# mainboard_valdis.net
KiCad netlist of a schematic drawn in Altium Designer
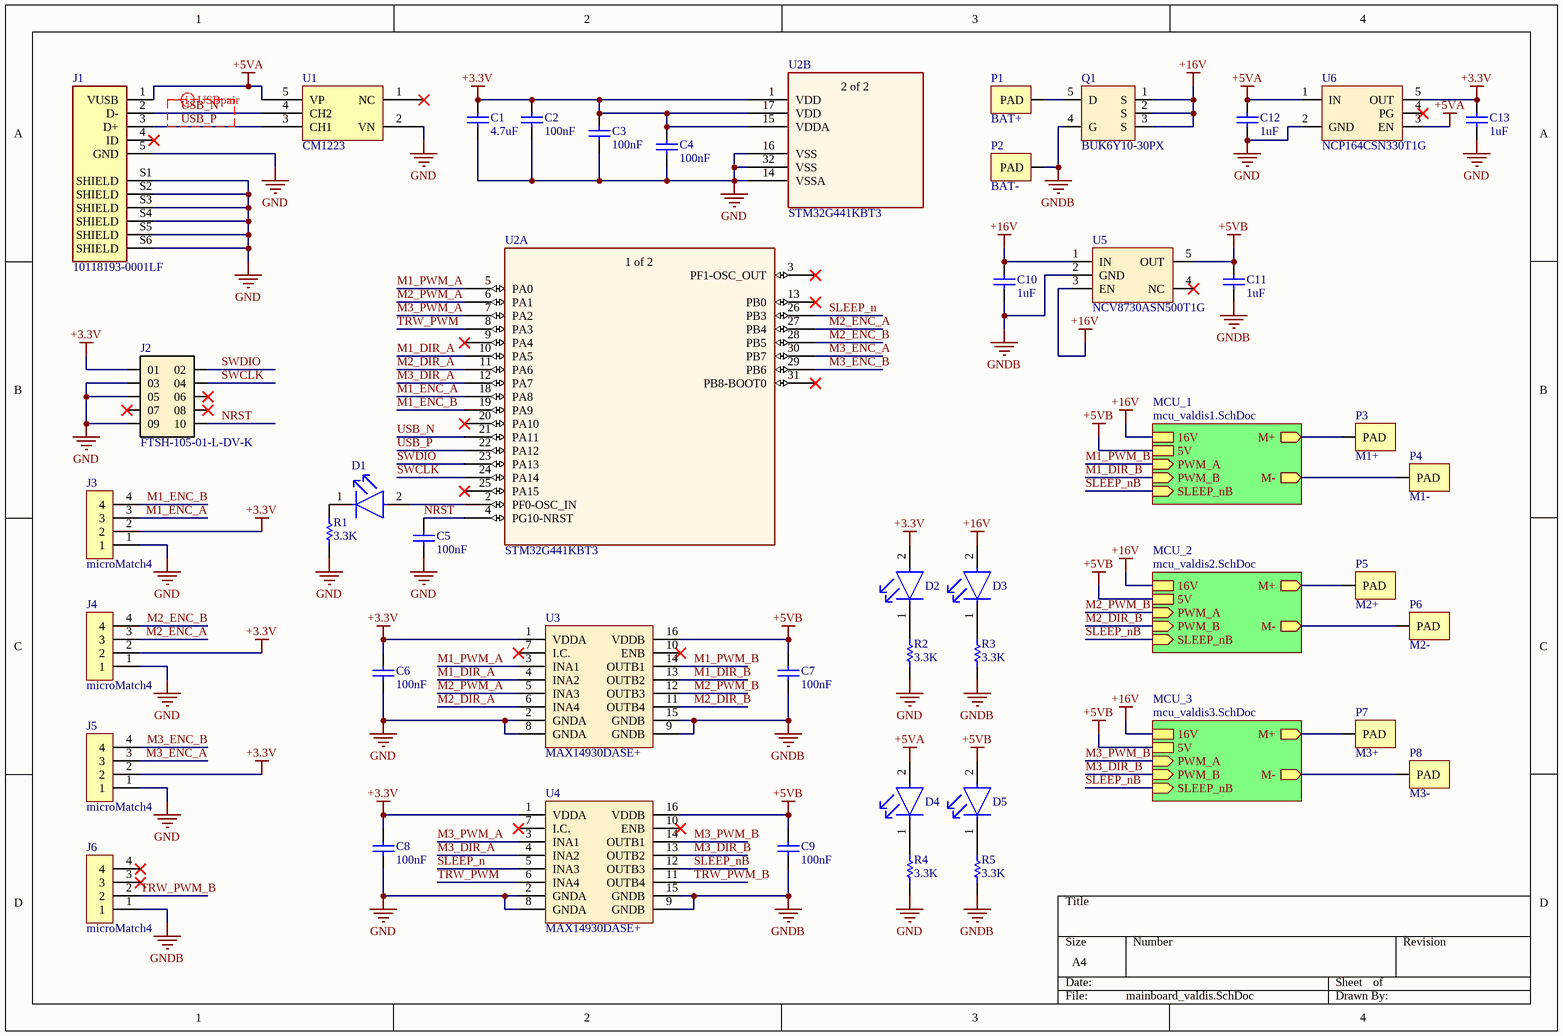
[diagram p0: mainboard_valdis.SchDoc]

(export (version "E")
  (design (tool "Eeschema 10.0.6"))
  (components
    (comp (ref "C1")
      (value "4.7uF")
      (footprint "CAPC1608X90X35ML10T15")
      (description "Chip Capacitor, 22 pF, +/- 5%, 50 V, -55 to 125 degC, 0603 (1608 Metric), RoHS, Tape and Reel")
      (fields (field (name "MANUFACTURER") "Murata"))
      (libsource (lib "Altium Content Vault") (part "CAP-NP-2"))
    )
    (comp (ref "C2")
      (value "100nF")
      (footprint "CAPC1608X90X35ML10T15")
      (description "Chip Capacitor, 22 pF, +/- 5%, 50 V, -55 to 125 degC, 0603 (1608 Metric), RoHS, Tape and Reel")
      (fields (field (name "MANUFACTURER") "Murata"))
      (libsource (lib "Altium Content Vault") (part "CAP-NP-2"))
    )
    (comp (ref "C3")
      (value "100nF")
      (footprint "CAPC1608X90X35ML10T15")
      (description "Chip Capacitor, 22 pF, +/- 5%, 50 V, -55 to 125 degC, 0603 (1608 Metric), RoHS, Tape and Reel")
      (fields (field (name "MANUFACTURER") "Murata"))
      (libsource (lib "Altium Content Vault") (part "CAP-NP-2"))
    )
    (comp (ref "C4")
      (value "100nF")
      (footprint "CAPC1608X90X35ML10T15")
      (description "Chip Capacitor, 22 pF, +/- 5%, 50 V, -55 to 125 degC, 0603 (1608 Metric), RoHS, Tape and Reel")
      (fields (field (name "MANUFACTURER") "Murata"))
      (libsource (lib "Altium Content Vault") (part "CAP-NP-2"))
    )
    (comp (ref "C5")
      (value "100nF")
      (footprint "CAPC1608X90X35ML10T15")
      (description "Chip Capacitor, 22 pF, +/- 5%, 50 V, -55 to 125 degC, 0603 (1608 Metric), RoHS, Tape and Reel")
      (fields (field (name "MANUFACTURER") "Murata"))
      (libsource (lib "Altium Content Vault") (part "CAP-NP-2"))
    )
    (comp (ref "C6")
      (value "100nF")
      (footprint "CAPC1608X90X35ML10T15")
      (description "Chip Capacitor, 22 pF, +/- 5%, 50 V, -55 to 125 degC, 0603 (1608 Metric), RoHS, Tape and Reel")
      (fields (field (name "MANUFACTURER") "Murata"))
      (libsource (lib "Altium Content Vault") (part "CAP-NP-2"))
    )
    (comp (ref "C7")
      (value "100nF")
      (footprint "CAPC1608X90X35ML10T15")
      (description "Chip Capacitor, 22 pF, +/- 5%, 50 V, -55 to 125 degC, 0603 (1608 Metric), RoHS, Tape and Reel")
      (fields (field (name "MANUFACTURER") "Murata"))
      (libsource (lib "Altium Content Vault") (part "CAP-NP-2"))
    )
    (comp (ref "C8")
      (value "100nF")
      (footprint "CAPC1608X90X35ML10T15")
      (description "Chip Capacitor, 22 pF, +/- 5%, 50 V, -55 to 125 degC, 0603 (1608 Metric), RoHS, Tape and Reel")
      (fields (field (name "MANUFACTURER") "Murata"))
      (libsource (lib "Altium Content Vault") (part "CAP-NP-2"))
    )
    (comp (ref "C9")
      (value "100nF")
      (footprint "CAPC1608X90X35ML10T15")
      (description "Chip Capacitor, 22 pF, +/- 5%, 50 V, -55 to 125 degC, 0603 (1608 Metric), RoHS, Tape and Reel")
      (fields (field (name "MANUFACTURER") "Murata"))
      (libsource (lib "Altium Content Vault") (part "CAP-NP-2"))
    )
    (comp (ref "C10")
      (value "1uF")
      (footprint "CAPC1608X90X35ML10T15")
      (description "Chip Capacitor, 22 pF, +/- 5%, 50 V, -55 to 125 degC, 0603 (1608 Metric), RoHS, Tape and Reel")
      (fields (field (name "MANUFACTURER") "Murata"))
      (libsource (lib "Altium Content Vault") (part "CAP-NP-2"))
    )
    (comp (ref "C11")
      (value "1uF")
      (footprint "CAPC1608X90X35ML10T15")
      (description "Chip Capacitor, 22 pF, +/- 5%, 50 V, -55 to 125 degC, 0603 (1608 Metric), RoHS, Tape and Reel")
      (fields (field (name "MANUFACTURER") "Murata"))
      (libsource (lib "Altium Content Vault") (part "CAP-NP-2"))
    )
    (comp (ref "C12")
      (value "1uF")
      (footprint "CAPC1608X90X35ML10T15")
      (description "Chip Capacitor, 22 pF, +/- 5%, 50 V, -55 to 125 degC, 0603 (1608 Metric), RoHS, Tape and Reel")
      (fields (field (name "MANUFACTURER") "Murata"))
      (libsource (lib "Altium Content Vault") (part "CAP-NP-2"))
    )
    (comp (ref "C13")
      (value "1uF")
      (footprint "CAPC1608X90X35ML10T15")
      (description "Chip Capacitor, 22 pF, +/- 5%, 50 V, -55 to 125 degC, 0603 (1608 Metric), RoHS, Tape and Reel")
      (fields (field (name "MANUFACTURER") "Murata"))
      (libsource (lib "Altium Content Vault") (part "CAP-NP-2"))
    )
    (comp (ref "D1")
      (value "LTST-C191TBKT")
      (footprint "FP-LTST-C191TBKT-MFG")
      (description "LED BLUE CLEAR CHIP SMD")
      (libsource (lib "Altium Content Vault") (part "8706943c75ba83719d021d2fdc84c58"))
    )
    (comp (ref "D2")
      (value "LTST-C191TBKT")
      (footprint "FP-LTST-C191TBKT-MFG")
      (description "LED BLUE CLEAR CHIP SMD")
      (libsource (lib "Altium Content Vault") (part "8706943c75ba83719d021d2fdc84c58"))
    )
    (comp (ref "D3")
      (value "LTST-C191TBKT")
      (footprint "FP-LTST-C191TBKT-MFG")
      (description "LED BLUE CLEAR CHIP SMD")
      (libsource (lib "Altium Content Vault") (part "8706943c75ba83719d021d2fdc84c58"))
    )
    (comp (ref "D4")
      (value "LTST-C191TBKT")
      (footprint "FP-LTST-C191TBKT-MFG")
      (description "LED BLUE CLEAR CHIP SMD")
      (libsource (lib "Altium Content Vault") (part "8706943c75ba83719d021d2fdc84c58"))
    )
    (comp (ref "D5")
      (value "LTST-C191TBKT")
      (footprint "FP-LTST-C191TBKT-MFG")
      (description "LED BLUE CLEAR CHIP SMD")
      (libsource (lib "Altium Content Vault") (part "8706943c75ba83719d021d2fdc84c58"))
    )
    (comp (ref "J1")
      (value "10118193-0001LF")
      (footprint "FCI_10118193-0001LF")
      (description "USB - micro B USB 2.0 Receptacle Connector 5 Position Surface Mount, Right Angle; Through Hole")
      (fields (field (name "MF") "Amphenol ICC"))
      (libsource (lib "Valdis_Components") (part "10118193-0001LF"))
    )
    (comp (ref "J2")
      (value "FTSH-105-01-L-DV-K")
      (footprint "FTSH-105-01-XXX-DV-K")
      (libsource (lib "Valdis_Components") (part "FTSH-105-01-L-DV-K"))
    )
    (comp (ref "J3")
      (value "microMatch4")
      (footprint "microMatch4:microMatch4")
      (libsource (lib "Valdis_Components") (part "microMatch4"))
    )
    (comp (ref "J4")
      (value "microMatch4")
      (footprint "microMatch4:microMatch4")
      (libsource (lib "Valdis_Components") (part "microMatch4"))
    )
    (comp (ref "J5")
      (value "microMatch4")
      (footprint "microMatch4:microMatch4")
      (libsource (lib "Valdis_Components") (part "microMatch4"))
    )
    (comp (ref "J6")
      (value "microMatch4")
      (footprint "microMatch4:microMatch4")
      (libsource (lib "Valdis_Components") (part "microMatch4"))
    )
    (comp (ref "P1") (value "BAT+") (footprint "PCBComponent_1") (libsource (lib "") (part "Pad4x4_1")))
    (comp (ref "P2") (value "BAT-") (footprint "PCBComponent_1") (libsource (lib "") (part "Pad4x4_1")))
    (comp (ref "P3")
      (value "M1+")
      (footprint "PCBComponent_1")
      (libsource (lib "Valdis_Components") (part "Pad4x4"))
    )
    (comp (ref "P4")
      (value "M1-")
      (footprint "PCBComponent_1")
      (libsource (lib "Valdis_Components") (part "Pad4x4"))
    )
    (comp (ref "P5")
      (value "M2+")
      (footprint "PCBComponent_1")
      (libsource (lib "Valdis_Components") (part "Pad4x4"))
    )
    (comp (ref "P6")
      (value "M2-")
      (footprint "PCBComponent_1")
      (libsource (lib "Valdis_Components") (part "Pad4x4"))
    )
    (comp (ref "P7")
      (value "M3+")
      (footprint "PCBComponent_1")
      (libsource (lib "Valdis_Components") (part "Pad4x4"))
    )
    (comp (ref "P8")
      (value "M3-")
      (footprint "PCBComponent_1")
      (libsource (lib "Valdis_Components") (part "Pad4x4"))
    )
    (comp (ref "Q1")
      (value "BUK6Y10-30PX")
      (footprint "TO127P600X120-5N")
      (libsource (lib "Valdis_Components") (part "BUK6Y10-30PX"))
    )
    (comp (ref "R1")
      (value "3.3K")
      (footprint "RESC1609X50X30NL8T20")
      (description "Chip Resistor, 0 Ohm, Jumper, 100 mW, -55 to 155 degC, 0603 (1608 Metric), RoHS, Tape and Reel")
      (fields (field (name "MANUFACTURER") "Vishay Semiconductor"))
      (libsource (lib "Altium Content Vault") (part "RES-2"))
    )
    (comp (ref "R2")
      (value "3.3K")
      (footprint "RESC1609X50X30NL8T20")
      (description "Chip Resistor, 0 Ohm, Jumper, 100 mW, -55 to 155 degC, 0603 (1608 Metric), RoHS, Tape and Reel")
      (fields (field (name "MANUFACTURER") "Vishay Semiconductor"))
      (libsource (lib "Altium Content Vault") (part "RES-2"))
    )
    (comp (ref "R3")
      (value "3.3K")
      (footprint "RESC1609X50X30NL8T20")
      (description "Chip Resistor, 0 Ohm, Jumper, 100 mW, -55 to 155 degC, 0603 (1608 Metric), RoHS, Tape and Reel")
      (fields (field (name "MANUFACTURER") "Vishay Semiconductor"))
      (libsource (lib "Altium Content Vault") (part "RES-2"))
    )
    (comp (ref "R4")
      (value "3.3K")
      (footprint "RESC1609X50X30NL8T20")
      (description "Chip Resistor, 0 Ohm, Jumper, 100 mW, -55 to 155 degC, 0603 (1608 Metric), RoHS, Tape and Reel")
      (fields (field (name "MANUFACTURER") "Vishay Semiconductor"))
      (libsource (lib "Altium Content Vault") (part "RES-2"))
    )
    (comp (ref "R5")
      (value "3.3K")
      (footprint "RESC1609X50X30NL8T20")
      (description "Chip Resistor, 0 Ohm, Jumper, 100 mW, -55 to 155 degC, 0603 (1608 Metric), RoHS, Tape and Reel")
      (fields (field (name "MANUFACTURER") "Vishay Semiconductor"))
      (libsource (lib "Altium Content Vault") (part "RES-2"))
    )
    (comp (ref "U1")
      (value "CM1223")
      (footprint "SOT23-5")
      (libsource (lib "Valdis_Components") (part "CM1223"))
    )
    (comp (ref "U2")
      (value "STM32G441KBT3")
      (footprint "LQFP32_7X7_STM")
      (description "No Description Available")
      (fields (field (name "COPYRIGHT") "Copyright (C) 2018 Accelerated Designs. All rights reserved"))
      (libsource (lib "") (part "STM32G441KBT3_1"))
    )
    (comp (ref "U3")
      (value "MAX14930DASE+")
      (footprint "21-0041_S16+1_MXM")
      (libsource (lib "Valdis_Components") (part "MAX14930DASE+"))
    )
    (comp (ref "U4")
      (value "MAX14930DASE+")
      (footprint "21-0041_S16+1_MXM")
      (libsource (lib "Valdis_Components") (part "MAX14930DASE+"))
    )
    (comp (ref "U5")
      (value "NCV8730ASN500T1G")
      (footprint "NCV8730:TSSOP5")
      (libsource (lib "NCV8730ASN500T1G") (part "NCV8730ASN500T1G"))
    )
    (comp (ref "U6")
      (value "NCP164CSN330T1G")
      (footprint "SOP95P275X110-5N")
      (libsource (lib "Valdis_Components") (part "NCP164CSN330T1G"))
    )
  )
  (nets
    (net (code "1") (name "+3.3V") (class "Default")
      (node (ref "C1") (pin "2") (pinfunction "2_2") (pintype "passive"))
      (node (ref "C13") (pin "2") (pinfunction "2_2") (pintype "passive"))
      (node (ref "C2") (pin "2") (pinfunction "2_2") (pintype "passive"))
      (node (ref "C3") (pin "2") (pinfunction "2_2") (pintype "passive"))
      (node (ref "C4") (pin "2") (pinfunction "2_2") (pintype "passive"))
      (node (ref "C6") (pin "2") (pinfunction "2_2") (pintype "passive"))
      (node (ref "C8") (pin "2") (pinfunction "2_2") (pintype "passive"))
      (node (ref "D2") (pin "2") (pinfunction "A_2") (pintype "passive"))
      (node (ref "J2") (pin "1") (pinfunction "01_1") (pintype "passive"))
      (node (ref "J3") (pin "2") (pinfunction "2_2") (pintype "passive"))
      (node (ref "J4") (pin "2") (pinfunction "2_2") (pintype "passive"))
      (node (ref "J5") (pin "2") (pinfunction "2_2") (pintype "passive"))
      (node (ref "U2") (pin "1") (pinfunction "VDD_1") (pintype "power_in"))
      (node (ref "U2") (pin "15") (pinfunction "VDDA_15") (pintype "power_in"))
      (node (ref "U2") (pin "17") (pinfunction "VDD_17") (pintype "power_in"))
      (node (ref "U3") (pin "1") (pinfunction "VDDA_1") (pintype "passive"))
      (node (ref "U4") (pin "1") (pinfunction "VDDA_1") (pintype "passive"))
      (node (ref "U6") (pin "5") (pinfunction "OUT_5") (pintype "passive"))
    )
    (net (code "2") (name "+5VA") (class "Default")
      (node (ref "C12") (pin "2") (pinfunction "2_2") (pintype "passive"))
      (node (ref "D4") (pin "2") (pinfunction "A_2") (pintype "passive"))
      (node (ref "J1") (pin "1") (pinfunction "VUSB_1") (pintype "passive"))
      (node (ref "U1") (pin "5") (pinfunction "VP_5") (pintype "passive"))
      (node (ref "U6") (pin "1") (pinfunction "IN_1") (pintype "passive"))
      (node (ref "U6") (pin "3") (pinfunction "EN_3") (pintype "passive"))
    )
    (net (code "3") (name "+5VB") (class "Default")
      (node (ref "C11") (pin "2") (pinfunction "2_2") (pintype "passive"))
      (node (ref "C7") (pin "2") (pinfunction "2_2") (pintype "passive"))
      (node (ref "C9") (pin "2") (pinfunction "2_2") (pintype "passive"))
      (node (ref "D5") (pin "2") (pinfunction "A_2") (pintype "passive"))
      (node (ref "U3") (pin "16") (pinfunction "VDDB_16") (pintype "passive"))
      (node (ref "U4") (pin "16") (pinfunction "VDDB_16") (pintype "passive"))
      (node (ref "U5") (pin "5") (pinfunction "OUT_5") (pintype "passive"))
    )
    (net (code "4") (name "+16V") (class "Default")
      (node (ref "C10") (pin "2") (pinfunction "2_2") (pintype "passive"))
      (node (ref "D3") (pin "2") (pinfunction "A_2") (pintype "passive"))
      (node (ref "Q1") (pin "1") (pinfunction "S_1") (pintype "passive"))
      (node (ref "Q1") (pin "2") (pinfunction "S_2") (pintype "passive"))
      (node (ref "Q1") (pin "3") (pinfunction "S_3") (pintype "passive"))
      (node (ref "U5") (pin "1") (pinfunction "IN_1") (pintype "passive"))
      (node (ref "U5") (pin "3") (pinfunction "EN_3") (pintype "passive"))
    )
    (net (code "5") (name "/M+") (class "Default")
      (node (ref "P7") (pin "1") (pinfunction "PAD_1") (pintype "passive"))
    )
    (net (code "6") (name "/M+_1") (class "Default")
      (node (ref "P3") (pin "1") (pinfunction "PAD_1") (pintype "passive"))
    )
    (net (code "7") (name "/M+_2") (class "Default")
      (node (ref "P5") (pin "1") (pinfunction "PAD_1") (pintype "passive"))
    )
    (net (code "8") (name "/M-") (class "Default")
      (node (ref "P8") (pin "1") (pinfunction "PAD_1") (pintype "passive"))
    )
    (net (code "9") (name "/M-_1") (class "Default")
      (node (ref "P4") (pin "1") (pinfunction "PAD_1") (pintype "passive"))
    )
    (net (code "10") (name "/M-_2") (class "Default")
      (node (ref "P6") (pin "1") (pinfunction "PAD_1") (pintype "passive"))
    )
    (net (code "11") (name "/M1_DIR_A") (class "Default")
      (node (ref "U2") (pin "10") (pinfunction "PA5_10") (pintype "bidirectional"))
      (node (ref "U3") (pin "4") (pinfunction "INA2_4") (pintype "passive"))
    )
    (net (code "12") (name "/M1_DIR_B") (class "Default")
      (node (ref "U3") (pin "13") (pinfunction "OUTB2_13") (pintype "passive"))
    )
    (net (code "13") (name "/M1_ENC_A") (class "Default")
      (node (ref "J3") (pin "3") (pinfunction "3_3") (pintype "passive"))
      (node (ref "U2") (pin "18") (pinfunction "PA8_18") (pintype "bidirectional"))
    )
    (net (code "14") (name "/M1_ENC_B") (class "Default")
      (node (ref "J3") (pin "4") (pinfunction "4_4") (pintype "passive"))
      (node (ref "U2") (pin "19") (pinfunction "PA9_19") (pintype "bidirectional"))
    )
    (net (code "15") (name "/M1_PWM_A") (class "Default")
      (node (ref "U2") (pin "5") (pinfunction "PA0_5") (pintype "bidirectional"))
      (node (ref "U3") (pin "3") (pinfunction "INA1_3") (pintype "passive"))
    )
    (net (code "16") (name "/M1_PWM_B") (class "Default")
      (node (ref "U3") (pin "14") (pinfunction "OUTB1_14") (pintype "passive"))
    )
    (net (code "17") (name "/M2_DIR_A") (class "Default")
      (node (ref "U2") (pin "11") (pinfunction "PA6_11") (pintype "bidirectional"))
      (node (ref "U3") (pin "6") (pinfunction "INA4_6") (pintype "passive"))
    )
    (net (code "18") (name "/M2_DIR_B") (class "Default")
      (node (ref "U3") (pin "11") (pinfunction "OUTB4_11") (pintype "passive"))
    )
    (net (code "19") (name "/M2_ENC_A") (class "Default")
      (node (ref "J4") (pin "3") (pinfunction "3_3") (pintype "passive"))
      (node (ref "U2") (pin "27") (pinfunction "PB4_27") (pintype "bidirectional"))
    )
    (net (code "20") (name "/M2_ENC_B") (class "Default")
      (node (ref "J4") (pin "4") (pinfunction "4_4") (pintype "passive"))
      (node (ref "U2") (pin "28") (pinfunction "PB5_28") (pintype "bidirectional"))
    )
    (net (code "21") (name "/M2_PWM_A") (class "Default")
      (node (ref "U2") (pin "6") (pinfunction "PA1_6") (pintype "bidirectional"))
      (node (ref "U3") (pin "5") (pinfunction "INA3_5") (pintype "passive"))
    )
    (net (code "22") (name "/M2_PWM_B") (class "Default")
      (node (ref "U3") (pin "12") (pinfunction "OUTB3_12") (pintype "passive"))
    )
    (net (code "23") (name "/M3_DIR_A") (class "Default")
      (node (ref "U2") (pin "12") (pinfunction "PA7_12") (pintype "bidirectional"))
      (node (ref "U4") (pin "4") (pinfunction "INA2_4") (pintype "passive"))
    )
    (net (code "24") (name "/M3_DIR_B") (class "Default")
      (node (ref "U4") (pin "13") (pinfunction "OUTB2_13") (pintype "passive"))
    )
    (net (code "25") (name "/M3_ENC_A") (class "Default")
      (node (ref "J5") (pin "3") (pinfunction "3_3") (pintype "passive"))
      (node (ref "U2") (pin "30") (pinfunction "PB7_30") (pintype "bidirectional"))
    )
    (net (code "26") (name "/M3_ENC_B") (class "Default")
      (node (ref "J5") (pin "4") (pinfunction "4_4") (pintype "passive"))
      (node (ref "U2") (pin "29") (pinfunction "PB6_29") (pintype "bidirectional"))
    )
    (net (code "27") (name "/M3_PWM_A") (class "Default")
      (node (ref "U2") (pin "7") (pinfunction "PA2_7") (pintype "bidirectional"))
      (node (ref "U4") (pin "3") (pinfunction "INA1_3") (pintype "passive"))
    )
    (net (code "28") (name "/M3_PWM_B") (class "Default")
      (node (ref "U4") (pin "14") (pinfunction "OUTB1_14") (pintype "passive"))
    )
    (net (code "29") (name "/NRST") (class "Default")
      (node (ref "C5") (pin "2") (pinfunction "2_2") (pintype "passive"))
      (node (ref "J2") (pin "10") (pinfunction "10_10") (pintype "passive"))
      (node (ref "U2") (pin "4") (pinfunction "PG10-NRST_4") (pintype "bidirectional"))
    )
    (net (code "30") (name "/SLEEP_n") (class "Default")
      (node (ref "U2") (pin "26") (pinfunction "PB3_26") (pintype "bidirectional"))
      (node (ref "U4") (pin "5") (pinfunction "INA3_5") (pintype "passive"))
    )
    (net (code "31") (name "/SLEEP_nB") (class "Default")
      (node (ref "U4") (pin "12") (pinfunction "OUTB3_12") (pintype "passive"))
    )
    (net (code "32") (name "/SWCLK") (class "Default")
      (node (ref "J2") (pin "4") (pinfunction "04_4") (pintype "passive"))
      (node (ref "U2") (pin "24") (pinfunction "PA14_24") (pintype "bidirectional"))
    )
    (net (code "33") (name "/SWDIO") (class "Default")
      (node (ref "J2") (pin "2") (pinfunction "02_2") (pintype "passive"))
      (node (ref "U2") (pin "23") (pinfunction "PA13_23") (pintype "bidirectional"))
    )
    (net (code "34") (name "/TRW_PWM") (class "Default")
      (node (ref "U2") (pin "8") (pinfunction "PA3_8") (pintype "bidirectional"))
      (node (ref "U4") (pin "6") (pinfunction "INA4_6") (pintype "passive"))
    )
    (net (code "35") (name "/TRW_PWM_B") (class "Default")
      (node (ref "J6") (pin "2") (pinfunction "2_2") (pintype "passive"))
      (node (ref "U4") (pin "11") (pinfunction "OUTB4_11") (pintype "passive"))
    )
    (net (code "36") (name "/USB_N") (class "Default")
      (node (ref "J1") (pin "2") (pinfunction "D-_2") (pintype "passive"))
      (node (ref "U1") (pin "4") (pinfunction "CH2_4") (pintype "passive"))
      (node (ref "U2") (pin "21") (pinfunction "PA11_21") (pintype "bidirectional"))
    )
    (net (code "37") (name "/USB_P") (class "Default")
      (node (ref "J1") (pin "3") (pinfunction "D+_3") (pintype "passive"))
      (node (ref "U1") (pin "3") (pinfunction "CH1_3") (pintype "passive"))
      (node (ref "U2") (pin "22") (pinfunction "PA12_22") (pintype "bidirectional"))
    )
    (net (code "38") (name "GND") (class "Default")
      (node (ref "C1") (pin "1") (pinfunction "1_1") (pintype "passive"))
      (node (ref "C12") (pin "1") (pinfunction "1_1") (pintype "passive"))
      (node (ref "C13") (pin "1") (pinfunction "1_1") (pintype "passive"))
      (node (ref "C2") (pin "1") (pinfunction "1_1") (pintype "passive"))
      (node (ref "C3") (pin "1") (pinfunction "1_1") (pintype "passive"))
      (node (ref "C4") (pin "1") (pinfunction "1_1") (pintype "passive"))
      (node (ref "C5") (pin "1") (pinfunction "1_1") (pintype "passive"))
      (node (ref "C6") (pin "1") (pinfunction "1_1") (pintype "passive"))
      (node (ref "C8") (pin "1") (pinfunction "1_1") (pintype "passive"))
      (node (ref "J1") (pin "5") (pinfunction "GND_5") (pintype "passive"))
      (node (ref "J1") (pin "S1") (pinfunction "SHIELD_S1") (pintype "passive"))
      (node (ref "J1") (pin "S2") (pinfunction "SHIELD_S2") (pintype "passive"))
      (node (ref "J1") (pin "S3") (pinfunction "SHIELD_S3") (pintype "passive"))
      (node (ref "J1") (pin "S4") (pinfunction "SHIELD_S4") (pintype "passive"))
      (node (ref "J1") (pin "S5") (pinfunction "SHIELD_S5") (pintype "passive"))
      (node (ref "J1") (pin "S6") (pinfunction "SHIELD_S6") (pintype "passive"))
      (node (ref "J2") (pin "3") (pinfunction "03_3") (pintype "passive"))
      (node (ref "J2") (pin "5") (pinfunction "05_5") (pintype "passive"))
      (node (ref "J2") (pin "9") (pinfunction "09_9") (pintype "passive"))
      (node (ref "J3") (pin "1") (pinfunction "1_1") (pintype "passive"))
      (node (ref "J4") (pin "1") (pinfunction "1_1") (pintype "passive"))
      (node (ref "J5") (pin "1") (pinfunction "1_1") (pintype "passive"))
      (node (ref "R1") (pin "1") (pinfunction "1_1") (pintype "passive"))
      (node (ref "R2") (pin "1") (pinfunction "1_1") (pintype "passive"))
      (node (ref "R4") (pin "1") (pinfunction "1_1") (pintype "passive"))
      (node (ref "U1") (pin "2") (pinfunction "VN_2") (pintype "passive"))
      (node (ref "U2") (pin "14") (pinfunction "VSSA_14") (pintype "passive"))
      (node (ref "U2") (pin "16") (pinfunction "VSS_16") (pintype "passive"))
      (node (ref "U2") (pin "32") (pinfunction "VSS_32") (pintype "passive"))
      (node (ref "U3") (pin "2") (pinfunction "GNDA_2") (pintype "passive"))
      (node (ref "U3") (pin "8") (pinfunction "GNDA_8") (pintype "passive"))
      (node (ref "U4") (pin "2") (pinfunction "GNDA_2") (pintype "passive"))
      (node (ref "U4") (pin "8") (pinfunction "GNDA_8") (pintype "passive"))
      (node (ref "U6") (pin "2") (pinfunction "GND_2") (pintype "passive"))
    )
    (net (code "39") (name "GNDB") (class "Default")
      (node (ref "C10") (pin "1") (pinfunction "1_1") (pintype "passive"))
      (node (ref "C11") (pin "1") (pinfunction "1_1") (pintype "passive"))
      (node (ref "C7") (pin "1") (pinfunction "1_1") (pintype "passive"))
      (node (ref "C9") (pin "1") (pinfunction "1_1") (pintype "passive"))
      (node (ref "J6") (pin "1") (pinfunction "1_1") (pintype "passive"))
      (node (ref "P2") (pin "1") (pinfunction "PAD_1") (pintype "passive"))
      (node (ref "Q1") (pin "4") (pinfunction "G_4") (pintype "passive"))
      (node (ref "R3") (pin "1") (pinfunction "1_1") (pintype "passive"))
      (node (ref "R5") (pin "1") (pinfunction "1_1") (pintype "passive"))
      (node (ref "U3") (pin "15") (pinfunction "GNDB_15") (pintype "passive"))
      (node (ref "U3") (pin "9") (pinfunction "GNDB_9") (pintype "passive"))
      (node (ref "U4") (pin "15") (pinfunction "GNDB_15") (pintype "passive"))
      (node (ref "U4") (pin "9") (pinfunction "GNDB_9") (pintype "passive"))
      (node (ref "U5") (pin "2") (pinfunction "GND_2") (pintype "passive"))
    )
    (net (code "40") (name "Net-(D1-A)") (class "Default")
      (node (ref "D1") (pin "2") (pinfunction "A_2") (pintype "passive"))
      (node (ref "U2") (pin "2") (pinfunction "PF0-OSC_IN_2") (pintype "bidirectional"))
    )
    (net (code "41") (name "Net-(D1-C)") (class "Default")
      (node (ref "D1") (pin "1") (pinfunction "C_1") (pintype "passive"))
      (node (ref "R1") (pin "2") (pinfunction "2_2") (pintype "passive"))
    )
    (net (code "42") (name "Net-(D2-C)") (class "Default")
      (node (ref "D2") (pin "1") (pinfunction "C_1") (pintype "passive"))
      (node (ref "R2") (pin "2") (pinfunction "2_2") (pintype "passive"))
    )
    (net (code "43") (name "Net-(D3-C)") (class "Default")
      (node (ref "D3") (pin "1") (pinfunction "C_1") (pintype "passive"))
      (node (ref "R3") (pin "2") (pinfunction "2_2") (pintype "passive"))
    )
    (net (code "44") (name "Net-(D4-C)") (class "Default")
      (node (ref "D4") (pin "1") (pinfunction "C_1") (pintype "passive"))
      (node (ref "R4") (pin "2") (pinfunction "2_2") (pintype "passive"))
    )
    (net (code "45") (name "Net-(D5-C)") (class "Default")
      (node (ref "D5") (pin "1") (pinfunction "C_1") (pintype "passive"))
      (node (ref "R5") (pin "2") (pinfunction "2_2") (pintype "passive"))
    )
    (net (code "46") (name "Net-(P1-PAD)") (class "Default")
      (node (ref "P1") (pin "1") (pinfunction "PAD_1") (pintype "passive"))
      (node (ref "Q1") (pin "5") (pinfunction "D_5") (pintype "passive"))
    )
    (net (code "47") (name "unconnected-(J1-ID-Pad4)") (class "Default")
      (node (ref "J1") (pin "4") (pinfunction "ID_4") (pintype "passive+no_connect"))
    )
    (net (code "48") (name "unconnected-(J2-06-Pad6)") (class "Default")
      (node (ref "J2") (pin "6") (pinfunction "06_6") (pintype "passive+no_connect"))
    )
    (net (code "49") (name "unconnected-(J2-07-Pad7)") (class "Default")
      (node (ref "J2") (pin "7") (pinfunction "07_7") (pintype "passive+no_connect"))
    )
    (net (code "50") (name "unconnected-(J2-08-Pad8)") (class "Default")
      (node (ref "J2") (pin "8") (pinfunction "08_8") (pintype "passive+no_connect"))
    )
    (net (code "51") (name "unconnected-(J6-Pad3)") (class "Default")
      (node (ref "J6") (pin "3") (pinfunction "3_3") (pintype "passive+no_connect"))
    )
    (net (code "52") (name "unconnected-(J6-Pad4)") (class "Default")
      (node (ref "J6") (pin "4") (pinfunction "4_4") (pintype "passive+no_connect"))
    )
    (net (code "53") (name "unconnected-(U1-NC-Pad1)") (class "Default")
      (node (ref "U1") (pin "1") (pinfunction "NC_1") (pintype "passive+no_connect"))
    )
    (net (code "54") (name "unconnected-(U2A-PA4-Pad9)") (class "Default")
      (node (ref "U2") (pin "9") (pinfunction "PA4_9") (pintype "bidirectional+no_connect"))
    )
    (net (code "55") (name "unconnected-(U2A-PA10-Pad20)") (class "Default")
      (node (ref "U2") (pin "20") (pinfunction "PA10_20") (pintype "bidirectional+no_connect"))
    )
    (net (code "56") (name "unconnected-(U2A-PA15-Pad25)") (class "Default")
      (node (ref "U2") (pin "25") (pinfunction "PA15_25") (pintype "bidirectional+no_connect"))
    )
    (net (code "57") (name "unconnected-(U2A-PB0-Pad13)") (class "Default")
      (node (ref "U2") (pin "13") (pinfunction "PB0_13") (pintype "bidirectional+no_connect"))
    )
    (net (code "58") (name "unconnected-(U2A-PB8-BOOT0-Pad31)") (class "Default")
      (node (ref "U2") (pin "31") (pinfunction "PB8-BOOT0_31") (pintype "bidirectional+no_connect"))
    )
    (net (code "59") (name "unconnected-(U2A-PF1-OSC_OUT-Pad3)") (class "Default")
      (node (ref "U2") (pin "3") (pinfunction "PF1-OSC_OUT_3") (pintype "bidirectional+no_connect"))
    )
    (net (code "60") (name "unconnected-(U3-ENB-Pad10)") (class "Default")
      (node (ref "U3") (pin "10") (pinfunction "ENB_10") (pintype "passive+no_connect"))
    )
    (net (code "61") (name "unconnected-(U3-I.C.-Pad7)") (class "Default")
      (node (ref "U3") (pin "7") (pinfunction "I.C._7") (pintype "passive+no_connect"))
    )
    (net (code "62") (name "unconnected-(U4-ENB-Pad10)") (class "Default")
      (node (ref "U4") (pin "10") (pinfunction "ENB_10") (pintype "passive+no_connect"))
    )
    (net (code "63") (name "unconnected-(U4-I.C.-Pad7)") (class "Default")
      (node (ref "U4") (pin "7") (pinfunction "I.C._7") (pintype "passive+no_connect"))
    )
    (net (code "64") (name "unconnected-(U5-NC-Pad4)") (class "Default")
      (node (ref "U5") (pin "4") (pinfunction "NC_4") (pintype "passive+no_connect"))
    )
    (net (code "65") (name "unconnected-(U6-PG-Pad4)") (class "Default")
      (node (ref "U6") (pin "4") (pinfunction "PG_4") (pintype "passive+no_connect"))
    )
  )
)
